# Schematic_v9.net
KiCad netlist of a schematic drawn in EAGLE
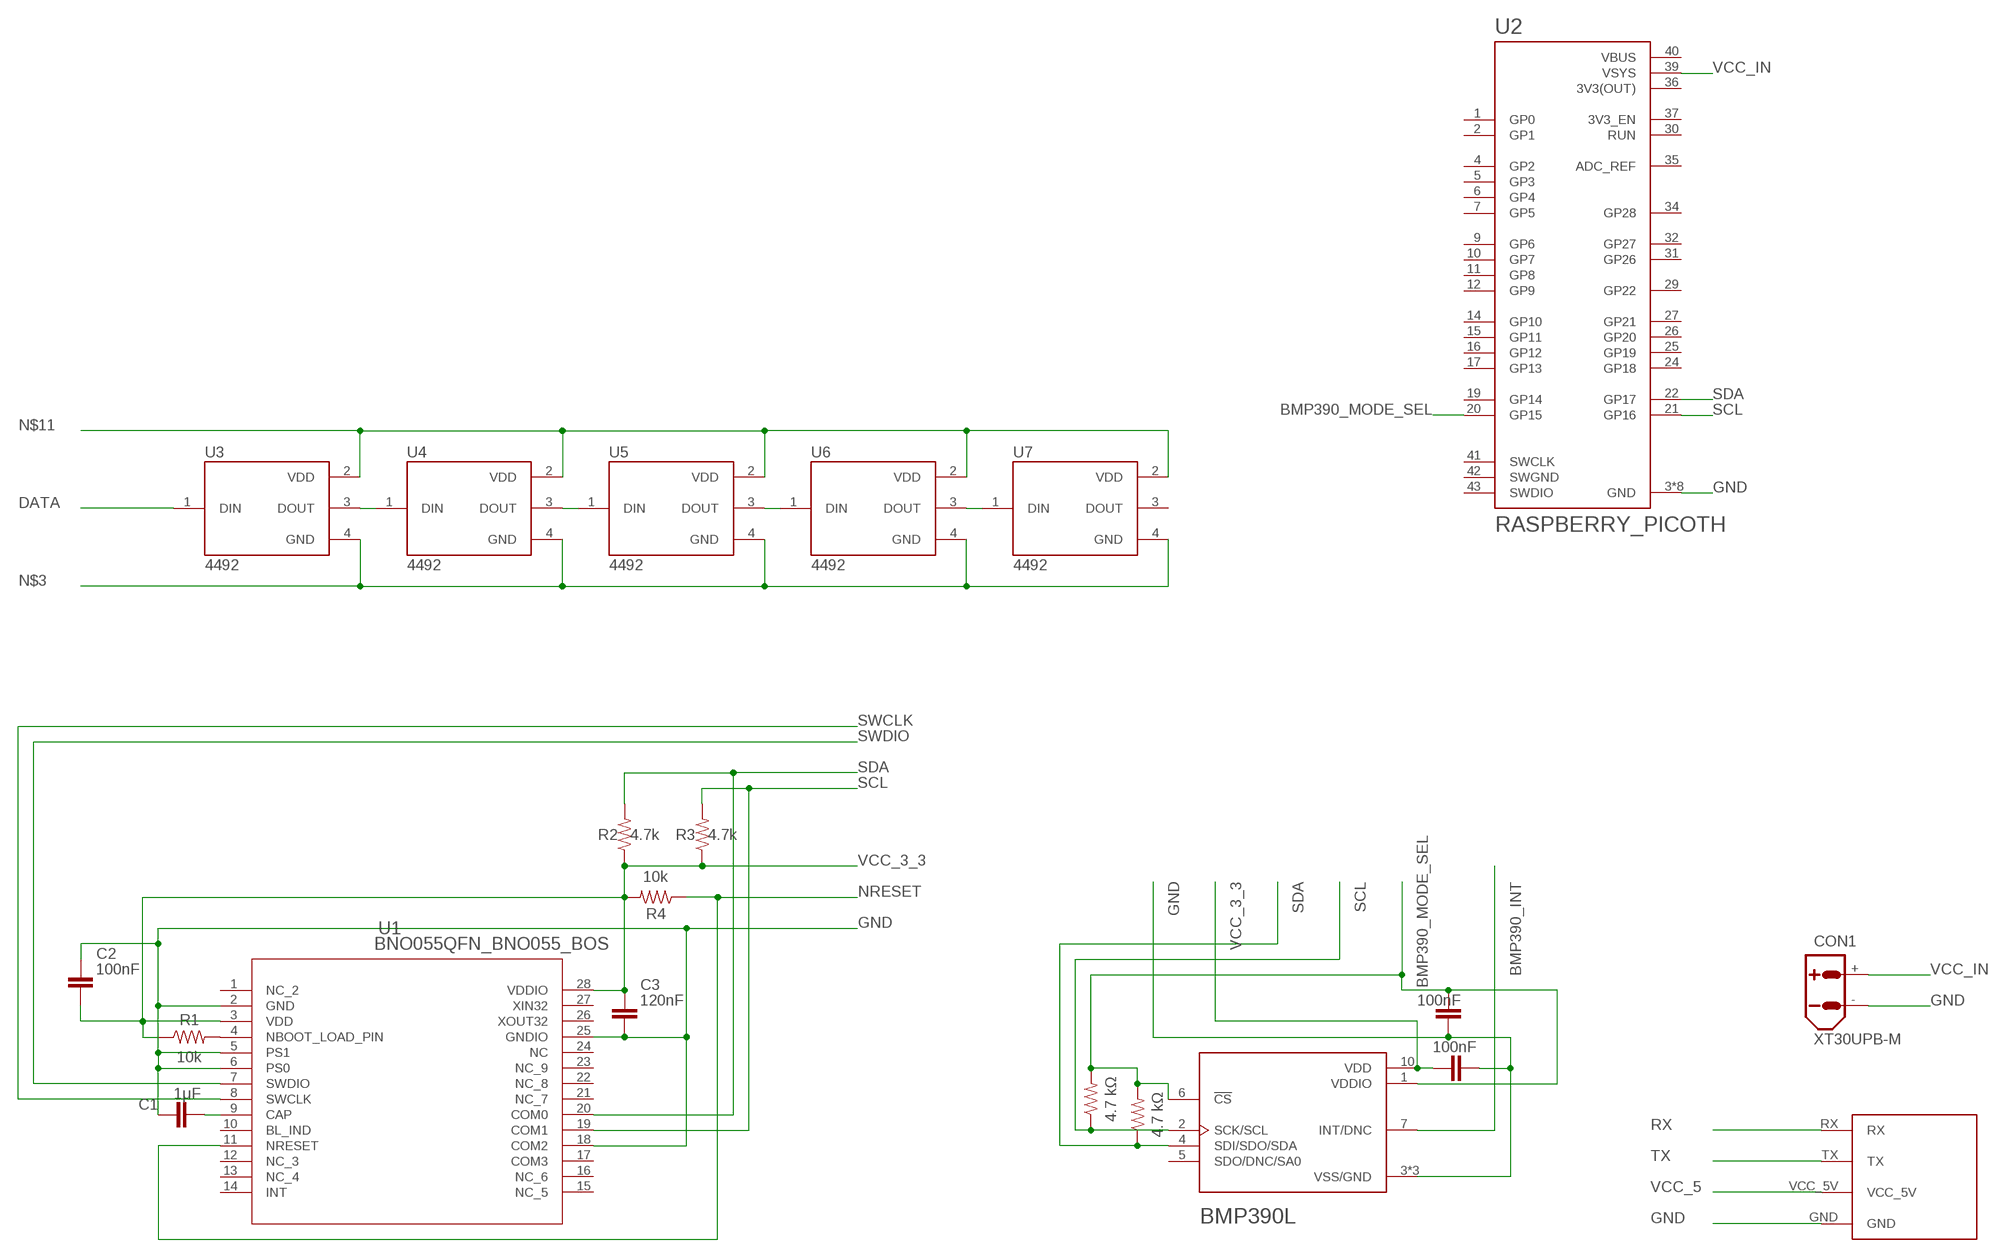
[diagram p0: schematic, sheet 1]

(export (version "E")
  (design (tool "Eeschema 10.0.6"))
  (components
    (comp (ref "C1")
      (value "1μF")
      (footprint "eagle-import:CAPC3216X135")
      (libsource (lib "eagle-import") (part "CCHIP-1206(3216-METRIC)_"))
    )
    (comp (ref "C2")
      (value "100nF")
      (footprint "eagle-import:CAPC3216X135")
      (libsource (lib "eagle-import") (part "CCHIP-1206(3216-METRIC)_"))
    )
    (comp (ref "C3")
      (value "120nF")
      (footprint "eagle-import:CAPC3216X135")
      (libsource (lib "eagle-import") (part "CCHIP-1206(3216-METRIC)_"))
    )
    (comp (ref "C4")
      (value "100nF")
      (footprint "eagle-import:CAPC3216X135")
      (libsource (lib "eagle-import") (part "CCHIP-1206(3216-METRIC)_"))
    )
    (comp (ref "C5")
      (value "100nF")
      (footprint "eagle-import:CAPC3216X135")
      (libsource (lib "eagle-import") (part "CCHIP-1206(3216-METRIC)_"))
    )
    (comp (ref "CON1")
      (value "XT30UPB-M")
      (footprint "eagle-import:XT30UPB-M")
      (libsource (lib "eagle-import") (part "XT30UPB-M"))
    )
    (comp (ref "R1")
      (value "10k")
      (footprint "eagle-import:RESC3216X70")
      (libsource (lib "eagle-import") (part "R-USCHIP-1206(3216-METRIC)_"))
    )
    (comp (ref "R2")
      (value "4.7k")
      (footprint "eagle-import:RESC3216X70")
      (libsource (lib "eagle-import") (part "R-USCHIP-1206(3216-METRIC)_"))
    )
    (comp (ref "R3")
      (value "4.7k")
      (footprint "eagle-import:RESC3216X70")
      (libsource (lib "eagle-import") (part "R-USCHIP-1206(3216-METRIC)_"))
    )
    (comp (ref "R4")
      (value "10k")
      (footprint "eagle-import:RESC3216X70")
      (libsource (lib "eagle-import") (part "R-USCHIP-1206(3216-METRIC)_"))
    )
    (comp (ref "R5")
      (value "4.7 kΩ")
      (footprint "eagle-import:RESC3216X70")
      (libsource (lib "eagle-import") (part "R-USCHIP-1206(3216-METRIC)_"))
    )
    (comp (ref "R6")
      (value "4.7 kΩ")
      (footprint "eagle-import:RESC3216X70")
      (libsource (lib "eagle-import") (part "R-USCHIP-1206(3216-METRIC)_"))
    )
    (comp (ref "U$1")
      (value "EP1")
      (footprint "eagle-import:EP1_MODEL")
      (libsource (lib "eagle-import") (part "EP1"))
    )
    (comp (ref "U1")
      (value "BNO055QFN_BNO055_BOS")
      (footprint "eagle-import:QFN_BNO055_BOS")
      (fields
        (field (name "MANUFACTURER_PART_NUMBER") "BNO055")
        (field (name "COPYRIGHT") "Copyright (C) 2024 Ultra Librarian. All rights reserved.")
      )
      (libsource (lib "eagle-import") (part "BNO055QFN_BNO055_BOS"))
    )
    (comp (ref "U2")
      (value "RASPBERRY_PICOTH")
      (footprint "eagle-import:PICO-PKG-TH")
      (libsource (lib "eagle-import") (part "RASPBERRY_PICOTH"))
    )
    (comp (ref "U3")
      (value "4492")
      (footprint "eagle-import:LED_4492")
      (fields (field (name "MF") "Adafruit"))
      (libsource (lib "eagle-import") (part "4492"))
    )
    (comp (ref "U4")
      (value "4492")
      (footprint "eagle-import:LED_4492")
      (fields (field (name "MF") "Adafruit"))
      (libsource (lib "eagle-import") (part "4492"))
    )
    (comp (ref "U5")
      (value "4492")
      (footprint "eagle-import:LED_4492")
      (fields (field (name "MF") "Adafruit"))
      (libsource (lib "eagle-import") (part "4492"))
    )
    (comp (ref "U6")
      (value "4492")
      (footprint "eagle-import:LED_4492")
      (fields (field (name "MF") "Adafruit"))
      (libsource (lib "eagle-import") (part "4492"))
    )
    (comp (ref "U7")
      (value "4492")
      (footprint "eagle-import:LED_4492")
      (fields (field (name "MF") "Adafruit"))
      (libsource (lib "eagle-import") (part "4492"))
    )
    (comp (ref "U11")
      (value "BMP390L")
      (footprint "eagle-import:XDCR_BMP390L")
      (fields (field (name "MF") "Bosch Sensortec"))
      (libsource (lib "eagle-import") (part "BMP390L"))
    )
  )
  (nets
    (net (code "1") (name "/3V3(OUT)") (class "Default")
      (node (ref "U2") (pin "36") (pinfunction "3V3(OUT)_36") (pintype "power_in"))
    )
    (net (code "2") (name "/BMP390_INT") (class "Default")
      (node (ref "U11") (pin "7") (pinfunction "INT/DNC_7") (pintype "output"))
    )
    (net (code "3") (name "/BMP390_MODE_SEL") (class "Default")
      (node (ref "C5") (pin "1") (pinfunction "1_1") (pintype "passive"))
      (node (ref "R5") (pin "2") (pinfunction "2_2") (pintype "passive"))
      (node (ref "R6") (pin "2") (pinfunction "2_2") (pintype "passive"))
      (node (ref "U11") (pin "1") (pinfunction "VDDIO_1") (pintype "power_in"))
      (node (ref "U11") (pin "6") (pinfunction "~{CS}_6") (pintype "input"))
      (node (ref "U2") (pin "20") (pinfunction "GP15_20") (pintype "bidirectional"))
    )
    (net (code "4") (name "/DATA") (class "Default")
      (node (ref "U3") (pin "1") (pinfunction "DIN_1") (pintype "input"))
    )
    (net (code "5") (name "/GND") (class "Default")
      (node (ref "C1") (pin "1") (pinfunction "1_1") (pintype "passive"))
      (node (ref "C2") (pin "1") (pinfunction "1_1") (pintype "passive"))
      (node (ref "C3") (pin "2") (pinfunction "2_2") (pintype "passive"))
      (node (ref "C4") (pin "2") (pinfunction "2_2") (pintype "passive"))
      (node (ref "C5") (pin "2") (pinfunction "2_2") (pintype "passive"))
      (node (ref "CON1") (pin "-") (pinfunction "-_-") (pintype "power_in"))
      (node (ref "U$1") (pin "GND") (pinfunction "GND_GND") (pintype "bidirectional"))
      (node (ref "U1") (pin "18") (pinfunction "COM2_18") (pintype "bidirectional"))
      (node (ref "U1") (pin "2") (pinfunction "GND_2") (pintype "passive"))
      (node (ref "U1") (pin "25") (pinfunction "GNDIO_25") (pintype "passive"))
      (node (ref "U1") (pin "5") (pinfunction "PS1_5") (pintype "input"))
      (node (ref "U1") (pin "6") (pinfunction "PS0_6") (pintype "input"))
      (node (ref "U11") (pin "3") (pinfunction "VSS/GND_3") (pintype "power_in"))
      (node (ref "U11") (pin "8") (pinfunction "VSS/GND_8") (pintype "power_in"))
      (node (ref "U11") (pin "9") (pinfunction "VSS/GND_9") (pintype "power_in"))
      (node (ref "U2") (pin "13") (pinfunction "GND_13") (pintype "power_in"))
      (node (ref "U2") (pin "18") (pinfunction "GND_18") (pintype "power_in"))
      (node (ref "U2") (pin "23") (pinfunction "GND_23") (pintype "power_in"))
      (node (ref "U2") (pin "28") (pinfunction "GND_28") (pintype "power_in"))
      (node (ref "U2") (pin "3") (pinfunction "GND_3") (pintype "power_in"))
      (node (ref "U2") (pin "33") (pinfunction "GND_33") (pintype "power_in"))
      (node (ref "U2") (pin "38") (pinfunction "GND_38") (pintype "power_in"))
      (node (ref "U2") (pin "8") (pinfunction "GND_8") (pintype "power_in"))
    )
    (net (code "6") (name "/N$3") (class "Default")
      (node (ref "U3") (pin "4") (pinfunction "GND_4") (pintype "power_in"))
      (node (ref "U4") (pin "4") (pinfunction "GND_4") (pintype "power_in"))
      (node (ref "U5") (pin "4") (pinfunction "GND_4") (pintype "power_in"))
      (node (ref "U6") (pin "4") (pinfunction "GND_4") (pintype "power_in"))
      (node (ref "U7") (pin "4") (pinfunction "GND_4") (pintype "power_in"))
    )
    (net (code "7") (name "/N$11") (class "Default")
      (node (ref "U3") (pin "2") (pinfunction "VDD_2") (pintype "power_in"))
      (node (ref "U4") (pin "2") (pinfunction "VDD_2") (pintype "power_in"))
      (node (ref "U5") (pin "2") (pinfunction "VDD_2") (pintype "power_in"))
      (node (ref "U6") (pin "2") (pinfunction "VDD_2") (pintype "power_in"))
      (node (ref "U7") (pin "2") (pinfunction "VDD_2") (pintype "power_in"))
    )
    (net (code "8") (name "/NRESET") (class "Default")
      (node (ref "R4") (pin "1") (pinfunction "1_1") (pintype "passive"))
      (node (ref "U1") (pin "11") (pinfunction "NRESET_11") (pintype "passive"))
    )
    (net (code "9") (name "/RX") (class "Default")
      (node (ref "U$1") (pin "RX") (pinfunction "RX_RX") (pintype "bidirectional"))
    )
    (net (code "10") (name "/SCL") (class "Default")
      (node (ref "R3") (pin "2") (pinfunction "2_2") (pintype "passive"))
      (node (ref "R5") (pin "1") (pinfunction "1_1") (pintype "passive"))
      (node (ref "U1") (pin "19") (pinfunction "COM1_19") (pintype "bidirectional"))
      (node (ref "U11") (pin "2") (pinfunction "SCK/SCL_2") (pintype "input"))
      (node (ref "U2") (pin "21") (pinfunction "GP16_21") (pintype "bidirectional"))
    )
    (net (code "11") (name "/SDA") (class "Default")
      (node (ref "R2") (pin "2") (pinfunction "2_2") (pintype "passive"))
      (node (ref "R6") (pin "1") (pinfunction "1_1") (pintype "passive"))
      (node (ref "U1") (pin "20") (pinfunction "COM0_20") (pintype "bidirectional"))
      (node (ref "U11") (pin "4") (pinfunction "SDI/SDO/SDA_4") (pintype "bidirectional"))
      (node (ref "U2") (pin "22") (pinfunction "GP17_22") (pintype "bidirectional"))
    )
    (net (code "12") (name "/SWCLK") (class "Default")
      (node (ref "U1") (pin "8") (pinfunction "SWCLK_8") (pintype "input"))
    )
    (net (code "13") (name "/SWDIO") (class "Default")
      (node (ref "U1") (pin "7") (pinfunction "SWDIO_7") (pintype "bidirectional"))
    )
    (net (code "14") (name "/SWGND") (class "Default")
      (node (ref "U2") (pin "42") (pinfunction "SWGND_42") (pintype "power_in"))
    )
    (net (code "15") (name "/TX") (class "Default")
      (node (ref "U$1") (pin "TX") (pinfunction "TX_TX") (pintype "bidirectional"))
    )
    (net (code "16") (name "/VBUS") (class "Default")
      (node (ref "U2") (pin "40") (pinfunction "VBUS_40") (pintype "power_in"))
    )
    (net (code "17") (name "/VCC_3_3") (class "Default")
      (node (ref "C2") (pin "2") (pinfunction "2_2") (pintype "passive"))
      (node (ref "C3") (pin "1") (pinfunction "1_1") (pintype "passive"))
      (node (ref "C4") (pin "1") (pinfunction "1_1") (pintype "passive"))
      (node (ref "R1") (pin "1") (pinfunction "1_1") (pintype "passive"))
      (node (ref "R2") (pin "1") (pinfunction "1_1") (pintype "passive"))
      (node (ref "R3") (pin "1") (pinfunction "1_1") (pintype "passive"))
      (node (ref "R4") (pin "2") (pinfunction "2_2") (pintype "passive"))
      (node (ref "U1") (pin "28") (pinfunction "VDDIO_28") (pintype "power_in"))
      (node (ref "U1") (pin "3") (pinfunction "VDD_3") (pintype "power_in"))
      (node (ref "U11") (pin "10") (pinfunction "VDD_10") (pintype "power_in"))
    )
    (net (code "18") (name "/VCC_5") (class "Default")
      (node (ref "U$1") (pin "VCC_5V") (pinfunction "VCC_5V_VCC_5V") (pintype "bidirectional"))
    )
    (net (code "19") (name "/VCC_IN") (class "Default")
      (node (ref "CON1") (pin "+") (pinfunction "+_+") (pintype "power_in"))
      (node (ref "U2") (pin "39") (pinfunction "VSYS_39") (pintype "power_in"))
    )
    (net (code "20") (name "Net-(U1-CAP)") (class "Default")
      (node (ref "C1") (pin "2") (pinfunction "2_2") (pintype "passive"))
      (node (ref "U1") (pin "9") (pinfunction "CAP_9") (pintype "passive"))
    )
    (net (code "21") (name "Net-(U1-NBOOT_LOAD_PIN)") (class "Default")
      (node (ref "R1") (pin "2") (pinfunction "2_2") (pintype "passive"))
      (node (ref "U1") (pin "4") (pinfunction "NBOOT_LOAD_PIN_4") (pintype "input"))
    )
    (net (code "22") (name "Net-(U3-DOUT)") (class "Default")
      (node (ref "U3") (pin "3") (pinfunction "DOUT_3") (pintype "output"))
      (node (ref "U4") (pin "1") (pinfunction "DIN_1") (pintype "input"))
    )
    (net (code "23") (name "Net-(U4-DOUT)") (class "Default")
      (node (ref "U4") (pin "3") (pinfunction "DOUT_3") (pintype "output"))
      (node (ref "U5") (pin "1") (pinfunction "DIN_1") (pintype "input"))
    )
    (net (code "24") (name "Net-(U5-DOUT)") (class "Default")
      (node (ref "U5") (pin "3") (pinfunction "DOUT_3") (pintype "output"))
      (node (ref "U6") (pin "1") (pinfunction "DIN_1") (pintype "input"))
    )
    (net (code "25") (name "Net-(U6-DOUT)") (class "Default")
      (node (ref "U6") (pin "3") (pinfunction "DOUT_3") (pintype "output"))
      (node (ref "U7") (pin "1") (pinfunction "DIN_1") (pintype "input"))
    )
    (net (code "26") (name "unconnected-(U1-BL_IND-Pad10)") (class "Default")
      (node (ref "U1") (pin "10") (pinfunction "BL_IND_10") (pintype "output"))
    )
    (net (code "27") (name "unconnected-(U1-COM3-Pad17)") (class "Default")
      (node (ref "U1") (pin "17") (pinfunction "COM3_17") (pintype "input"))
    )
    (net (code "28") (name "unconnected-(U1-INT-Pad14)") (class "Default")
      (node (ref "U1") (pin "14") (pinfunction "INT_14") (pintype "output"))
    )
    (net (code "29") (name "unconnected-(U1-NC-Pad24)") (class "Default")
      (node (ref "U1") (pin "24") (pinfunction "NC_24") (pintype "no_connect"))
    )
    (net (code "30") (name "unconnected-(U1-NC_2-Pad1)") (class "Default")
      (node (ref "U1") (pin "1") (pinfunction "NC_2_1") (pintype "no_connect"))
    )
    (net (code "31") (name "unconnected-(U1-NC_3-Pad12)") (class "Default")
      (node (ref "U1") (pin "12") (pinfunction "NC_3_12") (pintype "no_connect"))
    )
    (net (code "32") (name "unconnected-(U1-NC_4-Pad13)") (class "Default")
      (node (ref "U1") (pin "13") (pinfunction "NC_4_13") (pintype "no_connect"))
    )
    (net (code "33") (name "unconnected-(U1-NC_5-Pad15)") (class "Default")
      (node (ref "U1") (pin "15") (pinfunction "NC_5_15") (pintype "no_connect"))
    )
    (net (code "34") (name "unconnected-(U1-NC_6-Pad16)") (class "Default")
      (node (ref "U1") (pin "16") (pinfunction "NC_6_16") (pintype "no_connect"))
    )
    (net (code "35") (name "unconnected-(U1-NC_7-Pad21)") (class "Default")
      (node (ref "U1") (pin "21") (pinfunction "NC_7_21") (pintype "no_connect"))
    )
    (net (code "36") (name "unconnected-(U1-NC_8-Pad22)") (class "Default")
      (node (ref "U1") (pin "22") (pinfunction "NC_8_22") (pintype "no_connect"))
    )
    (net (code "37") (name "unconnected-(U1-NC_9-Pad23)") (class "Default")
      (node (ref "U1") (pin "23") (pinfunction "NC_9_23") (pintype "no_connect"))
    )
    (net (code "38") (name "unconnected-(U1-XIN32-Pad27)") (class "Default")
      (node (ref "U1") (pin "27") (pinfunction "XIN32_27") (pintype "input"))
    )
    (net (code "39") (name "unconnected-(U1-XOUT32-Pad26)") (class "Default")
      (node (ref "U1") (pin "26") (pinfunction "XOUT32_26") (pintype "output"))
    )
    (net (code "40") (name "unconnected-(U2-3V3_EN-Pad37)") (class "Default")
      (node (ref "U2") (pin "37") (pinfunction "3V3_EN_37") (pintype "input"))
    )
    (net (code "41") (name "unconnected-(U2-ADC_REF-Pad35)") (class "Default")
      (node (ref "U2") (pin "35") (pinfunction "ADC_REF_35") (pintype "input"))
    )
    (net (code "42") (name "unconnected-(U2-GP0-Pad1)") (class "Default")
      (node (ref "U2") (pin "1") (pinfunction "GP0_1") (pintype "bidirectional"))
    )
    (net (code "43") (name "unconnected-(U2-GP1-Pad2)") (class "Default")
      (node (ref "U2") (pin "2") (pinfunction "GP1_2") (pintype "bidirectional"))
    )
    (net (code "44") (name "unconnected-(U2-GP2-Pad4)") (class "Default")
      (node (ref "U2") (pin "4") (pinfunction "GP2_4") (pintype "bidirectional"))
    )
    (net (code "45") (name "unconnected-(U2-GP3-Pad5)") (class "Default")
      (node (ref "U2") (pin "5") (pinfunction "GP3_5") (pintype "bidirectional"))
    )
    (net (code "46") (name "unconnected-(U2-GP4-Pad6)") (class "Default")
      (node (ref "U2") (pin "6") (pinfunction "GP4_6") (pintype "bidirectional"))
    )
    (net (code "47") (name "unconnected-(U2-GP5-Pad7)") (class "Default")
      (node (ref "U2") (pin "7") (pinfunction "GP5_7") (pintype "bidirectional"))
    )
    (net (code "48") (name "unconnected-(U2-GP6-Pad9)") (class "Default")
      (node (ref "U2") (pin "9") (pinfunction "GP6_9") (pintype "bidirectional"))
    )
    (net (code "49") (name "unconnected-(U2-GP7-Pad10)") (class "Default")
      (node (ref "U2") (pin "10") (pinfunction "GP7_10") (pintype "bidirectional"))
    )
    (net (code "50") (name "unconnected-(U2-GP8-Pad11)") (class "Default")
      (node (ref "U2") (pin "11") (pinfunction "GP8_11") (pintype "bidirectional"))
    )
    (net (code "51") (name "unconnected-(U2-GP9-Pad12)") (class "Default")
      (node (ref "U2") (pin "12") (pinfunction "GP9_12") (pintype "bidirectional"))
    )
    (net (code "52") (name "unconnected-(U2-GP10-Pad14)") (class "Default")
      (node (ref "U2") (pin "14") (pinfunction "GP10_14") (pintype "bidirectional"))
    )
    (net (code "53") (name "unconnected-(U2-GP11-Pad15)") (class "Default")
      (node (ref "U2") (pin "15") (pinfunction "GP11_15") (pintype "bidirectional"))
    )
    (net (code "54") (name "unconnected-(U2-GP12-Pad16)") (class "Default")
      (node (ref "U2") (pin "16") (pinfunction "GP12_16") (pintype "bidirectional"))
    )
    (net (code "55") (name "unconnected-(U2-GP13-Pad17)") (class "Default")
      (node (ref "U2") (pin "17") (pinfunction "GP13_17") (pintype "bidirectional"))
    )
    (net (code "56") (name "unconnected-(U2-GP14-Pad19)") (class "Default")
      (node (ref "U2") (pin "19") (pinfunction "GP14_19") (pintype "bidirectional"))
    )
    (net (code "57") (name "unconnected-(U2-GP18-Pad24)") (class "Default")
      (node (ref "U2") (pin "24") (pinfunction "GP18_24") (pintype "bidirectional"))
    )
    (net (code "58") (name "unconnected-(U2-GP19-Pad25)") (class "Default")
      (node (ref "U2") (pin "25") (pinfunction "GP19_25") (pintype "bidirectional"))
    )
    (net (code "59") (name "unconnected-(U2-GP20-Pad26)") (class "Default")
      (node (ref "U2") (pin "26") (pinfunction "GP20_26") (pintype "bidirectional"))
    )
    (net (code "60") (name "unconnected-(U2-GP21-Pad27)") (class "Default")
      (node (ref "U2") (pin "27") (pinfunction "GP21_27") (pintype "bidirectional"))
    )
    (net (code "61") (name "unconnected-(U2-GP22-Pad29)") (class "Default")
      (node (ref "U2") (pin "29") (pinfunction "GP22_29") (pintype "bidirectional"))
    )
    (net (code "62") (name "unconnected-(U2-GP26-Pad31)") (class "Default")
      (node (ref "U2") (pin "31") (pinfunction "GP26_31") (pintype "bidirectional"))
    )
    (net (code "63") (name "unconnected-(U2-GP27-Pad32)") (class "Default")
      (node (ref "U2") (pin "32") (pinfunction "GP27_32") (pintype "bidirectional"))
    )
    (net (code "64") (name "unconnected-(U2-GP28-Pad34)") (class "Default")
      (node (ref "U2") (pin "34") (pinfunction "GP28_34") (pintype "bidirectional"))
    )
    (net (code "65") (name "unconnected-(U2-RUN-Pad30)") (class "Default")
      (node (ref "U2") (pin "30") (pinfunction "RUN_30") (pintype "input"))
    )
    (net (code "66") (name "unconnected-(U2-SWCLK-Pad41)") (class "Default")
      (node (ref "U2") (pin "41") (pinfunction "SWCLK_41") (pintype "input"))
    )
    (net (code "67") (name "unconnected-(U2-SWDIO-Pad43)") (class "Default")
      (node (ref "U2") (pin "43") (pinfunction "SWDIO_43") (pintype "bidirectional"))
    )
    (net (code "68") (name "unconnected-(U7-DOUT-Pad3)") (class "Default")
      (node (ref "U7") (pin "3") (pinfunction "DOUT_3") (pintype "output"))
    )
    (net (code "69") (name "unconnected-(U11-SDO{slash}DNC{slash}SA0-Pad5)") (class "Default")
      (node (ref "U11") (pin "5") (pinfunction "SDO/DNC/SA0_5") (pintype "bidirectional"))
    )
  )
)
